# RAILbooster.net
KiCad netlist of a schematic drawn in EAGLE
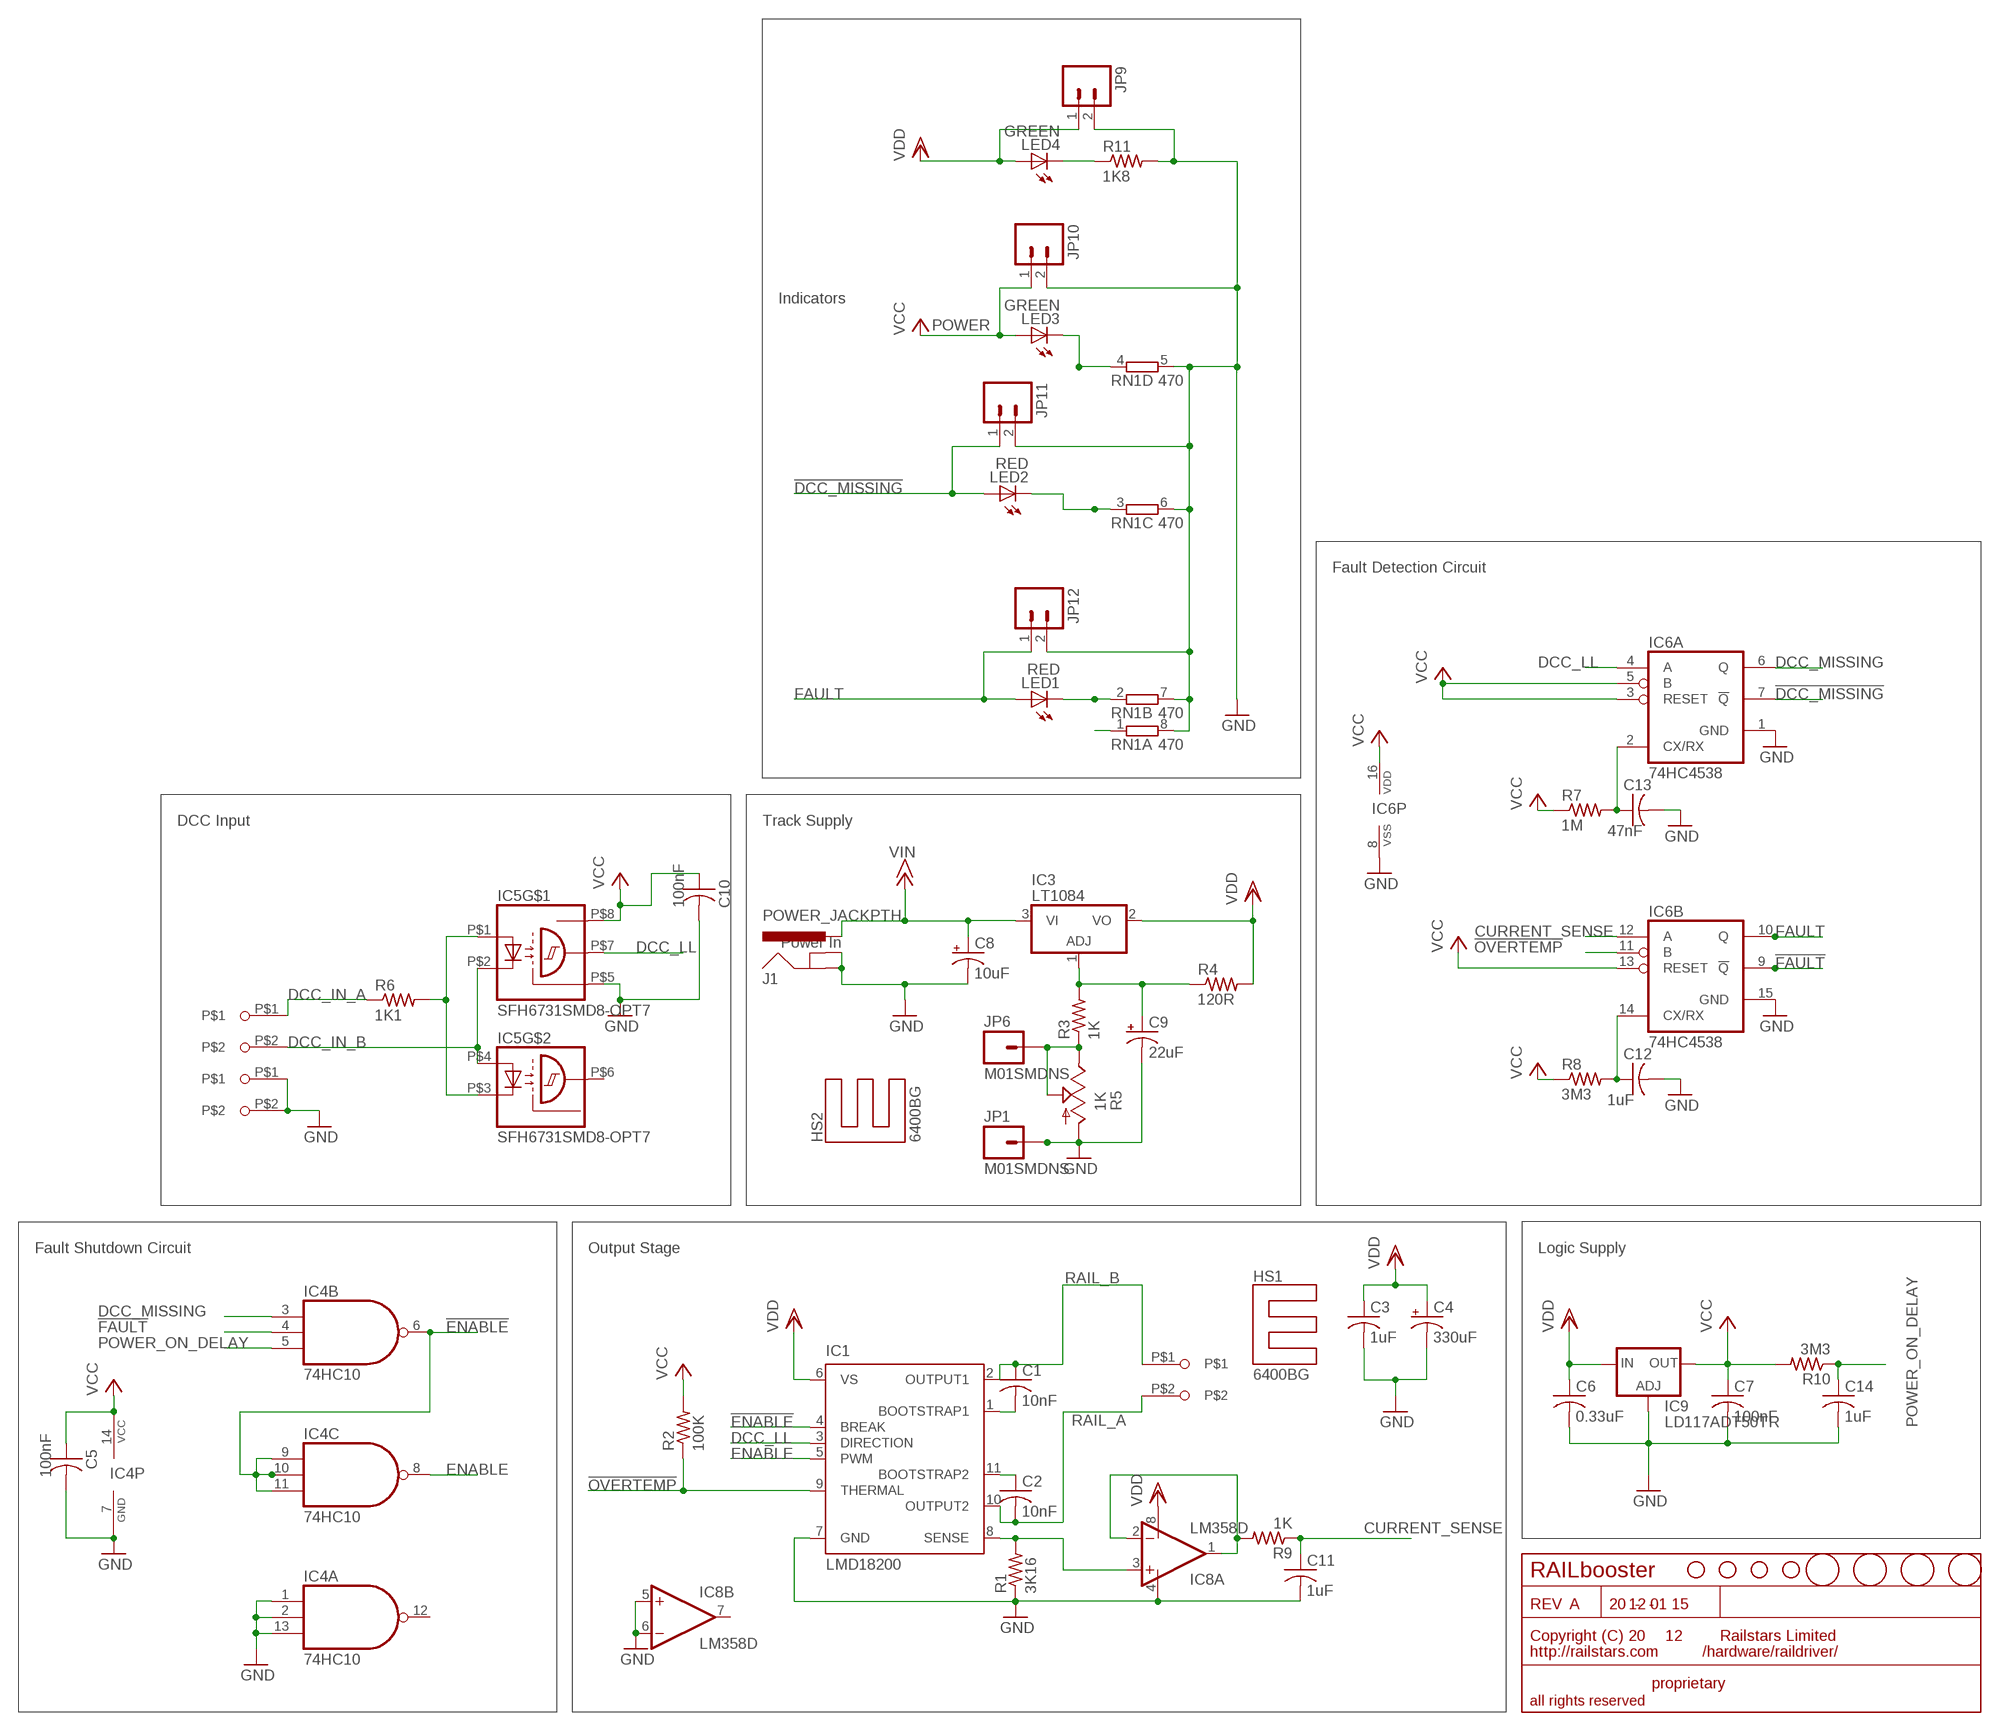
[diagram p0: schematic, sheet 1]

(export (version "E")
  (design (tool "Eeschema 10.0.6"))
  (components
    (comp (ref "C1")
      (value "10nF")
      (footprint "eagle-import:C0603")
      (libsource (lib "eagle-import") (part "C-USC0603"))
    )
    (comp (ref "C2")
      (value "10nF")
      (footprint "eagle-import:C0603")
      (libsource (lib "eagle-import") (part "C-USC0603"))
    )
    (comp (ref "C3")
      (value "1uF")
      (footprint "eagle-import:C0603")
      (libsource (lib "eagle-import") (part "C-USC0603"))
    )
    (comp (ref "C4")
      (value "330uF")
      (footprint "eagle-import:E5-10,5")
      (libsource (lib "eagle-import") (part "CPOL-USE5-10.5"))
    )
    (comp (ref "C5")
      (value "100nF")
      (footprint "eagle-import:C0603")
      (libsource (lib "eagle-import") (part "C-USC0603"))
    )
    (comp (ref "C6")
      (value "0.33uF")
      (footprint "eagle-import:C0603")
      (libsource (lib "eagle-import") (part "C-USC0603"))
    )
    (comp (ref "C7")
      (value "100nF")
      (footprint "eagle-import:C0603")
      (libsource (lib "eagle-import") (part "C-USC0603"))
    )
    (comp (ref "C8")
      (value "10uF")
      (footprint "eagle-import:E2-5")
      (libsource (lib "eagle-import") (part "CPOL-USE2-5"))
    )
    (comp (ref "C9")
      (value "22uF")
      (footprint "eagle-import:E2-5")
      (libsource (lib "eagle-import") (part "CPOL-USE2-5"))
    )
    (comp (ref "C10")
      (value "100nF")
      (footprint "eagle-import:C0603")
      (libsource (lib "eagle-import") (part "C-USC0603"))
    )
    (comp (ref "C11")
      (value "1uF")
      (footprint "eagle-import:C0603")
      (libsource (lib "eagle-import") (part "C-USC0603"))
    )
    (comp (ref "C12")
      (value "1uF")
      (footprint "eagle-import:C0603")
      (libsource (lib "eagle-import") (part "C-USC0603"))
    )
    (comp (ref "C13")
      (value "47nF")
      (footprint "eagle-import:C0603")
      (libsource (lib "eagle-import") (part "C-USC0603"))
    )
    (comp (ref "C14")
      (value "1uF")
      (footprint "eagle-import:C0603")
      (libsource (lib "eagle-import") (part "C-USC0603"))
    )
    (comp (ref "HS1")
      (value "6400BG")
      (footprint "eagle-import:6400BG")
      (libsource (lib "eagle-import") (part "HEATSINK6400BG"))
    )
    (comp (ref "HS2")
      (value "6400BG")
      (footprint "eagle-import:6400BG")
      (libsource (lib "eagle-import") (part "HEATSINK6400BG"))
    )
    (comp (ref "IC1")
      (value "LMD18200")
      (footprint "eagle-import:TO-220-11")
      (libsource (lib "eagle-import") (part "LM18200T"))
    )
    (comp (ref "IC3")
      (value "LT1084")
      (footprint "eagle-import:TO-220")
      (libsource (lib "eagle-import") (part "LT1084CT"))
    )
    (comp (ref "IC4")
      (value "74HC10")
      (footprint "eagle-import:SO14")
      (libsource (lib "eagle-import") (part "7410D"))
    )
    (comp (ref "IC5")
      (value "SFH6731SMD8-OPT7")
      (footprint "eagle-import:SMD8-OPT7")
      (libsource (lib "eagle-import") (part "SFH6731SMD8-OPT7"))
    )
    (comp (ref "IC6")
      (value "74HC4538")
      (footprint "eagle-import:SOIC-16")
      (libsource (lib "eagle-import") (part "74HC4538SOIC"))
    )
    (comp (ref "IC8")
      (value "LM358D")
      (footprint "eagle-import:SO08")
      (libsource (lib "eagle-import") (part "LM358D"))
    )
    (comp (ref "IC9")
      (value "LD117ADT50TR")
      (footprint "eagle-import:DPACK")
      (libsource (lib "eagle-import") (part "LD117A?DT50TR"))
    )
    (comp (ref "J1")
      (value "POWER_JACKPTH")
      (footprint "eagle-import:POWER_JACK_PTH")
      (libsource (lib "eagle-import") (part "POWER_JACKPTH"))
    )
    (comp (ref "JP1")
      (value "M01SMDNS")
      (footprint "eagle-import:1X01NS")
      (libsource (lib "eagle-import") (part "M01SMDNS"))
    )
    (comp (ref "JP2")
      (value "STAND-OFF")
      (footprint "eagle-import:STAND-OFF")
      (libsource (lib "eagle-import") (part "STAND-OFF"))
    )
    (comp (ref "JP3")
      (value "STAND-OFF")
      (footprint "eagle-import:STAND-OFF")
      (libsource (lib "eagle-import") (part "STAND-OFF"))
    )
    (comp (ref "JP4")
      (value "STAND-OFF")
      (footprint "eagle-import:STAND-OFF")
      (libsource (lib "eagle-import") (part "STAND-OFF"))
    )
    (comp (ref "JP5")
      (value "STAND-OFF")
      (footprint "eagle-import:STAND-OFF")
      (libsource (lib "eagle-import") (part "STAND-OFF"))
    )
    (comp (ref "JP6")
      (value "M01SMDNS")
      (footprint "eagle-import:1X01NS")
      (libsource (lib "eagle-import") (part "M01SMDNS"))
    )
    (comp (ref "JP9")
      (value "M02PTH")
      (footprint "eagle-import:1X02")
      (libsource (lib "eagle-import") (part "M02PTH"))
    )
    (comp (ref "JP10")
      (value "M02PTH")
      (footprint "eagle-import:1X02")
      (libsource (lib "eagle-import") (part "M02PTH"))
    )
    (comp (ref "JP11")
      (value "M02PTH")
      (footprint "eagle-import:1X02")
      (libsource (lib "eagle-import") (part "M02PTH"))
    )
    (comp (ref "JP12")
      (value "M02PTH")
      (footprint "eagle-import:1X02")
      (libsource (lib "eagle-import") (part "M02PTH"))
    )
    (comp (ref "LED1")
      (value "RED")
      (footprint "eagle-import:LED-0603")
      (libsource (lib "eagle-import") (part "LED0603"))
    )
    (comp (ref "LED2")
      (value "RED")
      (footprint "eagle-import:LED-0603")
      (libsource (lib "eagle-import") (part "LED0603"))
    )
    (comp (ref "LED3")
      (value "GREEN")
      (footprint "eagle-import:LED-0603")
      (libsource (lib "eagle-import") (part "LED0603"))
    )
    (comp (ref "LED4")
      (value "GREEN")
      (footprint "eagle-import:LED-0603")
      (libsource (lib "eagle-import") (part "LED0603"))
    )
    (comp (ref "R1")
      (value "3K16")
      (footprint "eagle-import:R0603")
      (libsource (lib "eagle-import") (part "R-US_R0603"))
    )
    (comp (ref "R2")
      (value "100K")
      (footprint "eagle-import:R0603")
      (libsource (lib "eagle-import") (part "R-US_R0603"))
    )
    (comp (ref "R3")
      (value "1K")
      (footprint "eagle-import:R1206")
      (libsource (lib "eagle-import") (part "R-US_R1206"))
    )
    (comp (ref "R4")
      (value "120R")
      (footprint "eagle-import:R0603")
      (libsource (lib "eagle-import") (part "R-US_R0603"))
    )
    (comp (ref "R5")
      (value "1K")
      (footprint "eagle-import:S64W")
      (libsource (lib "eagle-import") (part "TRIM_US-S64W"))
    )
    (comp (ref "R6")
      (value "1K1")
      (footprint "eagle-import:R1206")
      (libsource (lib "eagle-import") (part "R-US_R1206"))
    )
    (comp (ref "R7")
      (value "1M")
      (footprint "eagle-import:R0603")
      (libsource (lib "eagle-import") (part "R-US_R0603"))
    )
    (comp (ref "R8")
      (value "3M3")
      (footprint "eagle-import:R0603")
      (libsource (lib "eagle-import") (part "R-US_R0603"))
    )
    (comp (ref "R9")
      (value "1K")
      (footprint "eagle-import:R1206")
      (libsource (lib "eagle-import") (part "R-US_R1206"))
    )
    (comp (ref "R10")
      (value "3M3")
      (footprint "eagle-import:R0603")
      (libsource (lib "eagle-import") (part "R-US_R0603"))
    )
    (comp (ref "R11")
      (value "1K8")
      (footprint "eagle-import:R1206")
      (libsource (lib "eagle-import") (part "R-US_R1206"))
    )
    (comp (ref "RN1")
      (value "470")
      (footprint "eagle-import:EXBS8V")
      (libsource (lib "eagle-import") (part "4R-NEXBS8V"))
    )
    (comp (ref "U$1")
      (value "RAILSTARS_LOGO20MM")
      (footprint "eagle-import:RAILSTARS_1IN")
      (libsource (lib "eagle-import") (part "RAILSTARS_LOGO20MM"))
    )
    (comp (ref "U$5")
      (value "FIDUCIAL")
      (footprint "eagle-import:FIDUCIAL_1MM")
      (libsource (lib "eagle-import") (part "FIDUCIAL"))
    )
    (comp (ref "U$6")
      (value "FIDUCIAL")
      (footprint "eagle-import:FIDUCIAL_1MM")
      (libsource (lib "eagle-import") (part "FIDUCIAL"))
    )
    (comp (ref "U$7")
      (value "FIDUCIAL")
      (footprint "eagle-import:FIDUCIAL_1MM")
      (libsource (lib "eagle-import") (part "FIDUCIAL"))
    )
    (comp (ref "U$8")
      (value "FIDUCIAL")
      (footprint "eagle-import:FIDUCIAL_1MM")
      (libsource (lib "eagle-import") (part "FIDUCIAL"))
    )
    (comp (ref "X1")
      (value "SCREWTERMINAL-5.08-2")
      (footprint "eagle-import:SCREWTERMINAL-5.08-2")
      (libsource (lib "eagle-import") (part "SCREWTERMINAL-5.08-2"))
    )
    (comp (ref "X3")
      (value "SCREWTERMINAL-5.08-2")
      (footprint "eagle-import:SCREWTERMINAL-5.08-2")
      (libsource (lib "eagle-import") (part "SCREWTERMINAL-5.08-2"))
    )
    (comp (ref "X4")
      (value "SCREWTERMINAL-5.08-2")
      (footprint "eagle-import:SCREWTERMINAL-5.08-2")
      (libsource (lib "eagle-import") (part "SCREWTERMINAL-5.08-2"))
    )
  )
  (nets
    (net (code "1") (name "/CURRENT_SENSE") (class "Default")
      (node (ref "C11") (pin "1") (pinfunction "1_1") (pintype "passive"))
      (node (ref "IC6") (pin "12") (pinfunction "A_12") (pintype "input"))
      (node (ref "R9") (pin "1") (pinfunction "1_1") (pintype "passive"))
    )
    (net (code "2") (name "/DCC_IN_A") (class "Default")
      (node (ref "R6") (pin "1") (pinfunction "1_1") (pintype "passive"))
      (node (ref "X1") (pin "P$1") (pinfunction "P$1_P$1") (pintype "bidirectional"))
    )
    (net (code "3") (name "/DCC_IN_B") (class "Default")
      (node (ref "IC5") (pin "P$2") (pinfunction "C_P$2") (pintype "passive"))
      (node (ref "IC5") (pin "P$4") (pinfunction "A_P$4") (pintype "passive"))
      (node (ref "X1") (pin "P$2") (pinfunction "P$2_P$2") (pintype "bidirectional"))
    )
    (net (code "4") (name "/DCC_LL") (class "Default")
      (node (ref "IC1") (pin "3") (pinfunction "DIRECTION_3") (pintype "input"))
      (node (ref "IC5") (pin "P$7") (pinfunction "OUT_P$7") (pintype "passive"))
      (node (ref "IC6") (pin "4") (pinfunction "A_4") (pintype "input"))
    )
    (net (code "5") (name "/DCC_MISSING") (class "Default")
      (node (ref "IC4") (pin "3") (pinfunction "I0_3") (pintype "input"))
      (node (ref "IC6") (pin "6") (pinfunction "Q_6") (pintype "output"))
    )
    (net (code "6") (name "/ENABLE") (class "Default")
      (node (ref "IC1") (pin "5") (pinfunction "PWM_5") (pintype "input"))
      (node (ref "IC4") (pin "8") (pinfunction "O_8") (pintype "output"))
    )
    (net (code "7") (name "/FAULT") (class "Default")
      (node (ref "IC6") (pin "10") (pinfunction "Q_10") (pintype "output"))
      (node (ref "JP12") (pin "1") (pinfunction "1_1") (pintype "passive"))
      (node (ref "LED1") (pin "A") (pinfunction "A_A") (pintype "passive"))
    )
    (net (code "8") (name "/POWER_ON_DELAY") (class "Default")
      (node (ref "C14") (pin "1") (pinfunction "1_1") (pintype "passive"))
      (node (ref "IC4") (pin "5") (pinfunction "I2_5") (pintype "input"))
      (node (ref "R10") (pin "1") (pinfunction "1_1") (pintype "passive"))
    )
    (net (code "9") (name "/RAIL_A") (class "Default")
      (node (ref "C2") (pin "2") (pinfunction "2_2") (pintype "passive"))
      (node (ref "IC1") (pin "10") (pinfunction "OUTPUT2_10") (pintype "output"))
      (node (ref "X4") (pin "P$2") (pinfunction "P$2_P$2") (pintype "bidirectional"))
    )
    (net (code "10") (name "/RAIL_B") (class "Default")
      (node (ref "C1") (pin "1") (pinfunction "1_1") (pintype "passive"))
      (node (ref "IC1") (pin "2") (pinfunction "OUTPUT1_2") (pintype "output"))
      (node (ref "X4") (pin "P$1") (pinfunction "P$1_P$1") (pintype "bidirectional"))
    )
    (net (code "11") (name "/~{DCC_MISSING}") (class "Default")
      (node (ref "IC6") (pin "7") (pinfunction "~{Q}_7") (pintype "output"))
      (node (ref "JP11") (pin "1") (pinfunction "1_1") (pintype "passive"))
      (node (ref "LED2") (pin "A") (pinfunction "A_A") (pintype "passive"))
    )
    (net (code "12") (name "/~{ENABLE}") (class "Default")
      (node (ref "IC1") (pin "4") (pinfunction "BREAK_4") (pintype "input"))
      (node (ref "IC4") (pin "10") (pinfunction "I1_10") (pintype "input"))
      (node (ref "IC4") (pin "11") (pinfunction "I2_11") (pintype "input"))
      (node (ref "IC4") (pin "6") (pinfunction "O_6") (pintype "output"))
      (node (ref "IC4") (pin "9") (pinfunction "I0_9") (pintype "input"))
    )
    (net (code "13") (name "/~{FAULT}") (class "Default")
      (node (ref "IC4") (pin "4") (pinfunction "I1_4") (pintype "input"))
      (node (ref "IC6") (pin "9") (pinfunction "~{Q}_9") (pintype "output"))
    )
    (net (code "14") (name "/~{OVERTEMP}") (class "Default")
      (node (ref "IC1") (pin "9") (pinfunction "THERMAL_9") (pintype "output"))
      (node (ref "IC6") (pin "11") (pinfunction "B_11") (pintype "input"))
      (node (ref "R2") (pin "1") (pinfunction "1_1") (pintype "passive"))
    )
    (net (code "15") (name "GND") (class "Default")
      (node (ref "C10") (pin "2") (pinfunction "2_2") (pintype "passive"))
      (node (ref "C11") (pin "2") (pinfunction "2_2") (pintype "passive"))
      (node (ref "C12") (pin "2") (pinfunction "2_2") (pintype "passive"))
      (node (ref "C13") (pin "2") (pinfunction "2_2") (pintype "passive"))
      (node (ref "C14") (pin "2") (pinfunction "2_2") (pintype "passive"))
      (node (ref "C3") (pin "2") (pinfunction "2_2") (pintype "passive"))
      (node (ref "C4") (pin "-") (pinfunction "-_-") (pintype "passive"))
      (node (ref "C5") (pin "2") (pinfunction "2_2") (pintype "passive"))
      (node (ref "C6") (pin "2") (pinfunction "2_2") (pintype "passive"))
      (node (ref "C7") (pin "2") (pinfunction "2_2") (pintype "passive"))
      (node (ref "C8") (pin "-") (pinfunction "-_-") (pintype "passive"))
      (node (ref "C9") (pin "-") (pinfunction "-_-") (pintype "passive"))
      (node (ref "IC1") (pin "7") (pinfunction "GND_7") (pintype "power_in"))
      (node (ref "IC4") (pin "1") (pinfunction "I0_1") (pintype "input"))
      (node (ref "IC4") (pin "13") (pinfunction "I2_13") (pintype "input"))
      (node (ref "IC4") (pin "2") (pinfunction "I1_2") (pintype "input"))
      (node (ref "IC4") (pin "7") (pinfunction "GND_7") (pintype "power_in"))
      (node (ref "IC5") (pin "P$5") (pinfunction "GND_P$5") (pintype "passive"))
      (node (ref "IC6") (pin "1") (pinfunction "GND_1") (pintype "input"))
      (node (ref "IC6") (pin "15") (pinfunction "GND_15") (pintype "input"))
      (node (ref "IC6") (pin "8") (pinfunction "VSS_8") (pintype "power_in"))
      (node (ref "IC8") (pin "4") (pinfunction "V-_4") (pintype "power_in"))
      (node (ref "IC8") (pin "5") (pinfunction "+IN_5") (pintype "input"))
      (node (ref "IC8") (pin "6") (pinfunction "-IN_6") (pintype "input"))
      (node (ref "IC9") (pin "1") (pinfunction "ADJ_1") (pintype "input"))
      (node (ref "J1") (pin "GND") (pinfunction "GND_GND") (pintype "bidirectional"))
      (node (ref "J1") (pin "GNDBREAK") (pinfunction "GNDBREAK_GNDBREAK") (pintype "bidirectional"))
      (node (ref "JP1") (pin "1") (pinfunction "1_1") (pintype "passive"))
      (node (ref "JP10") (pin "2") (pinfunction "2_2") (pintype "passive"))
      (node (ref "JP11") (pin "2") (pinfunction "2_2") (pintype "passive"))
      (node (ref "JP12") (pin "2") (pinfunction "2_2") (pintype "passive"))
      (node (ref "JP9") (pin "2") (pinfunction "2_2") (pintype "passive"))
      (node (ref "R1") (pin "1") (pinfunction "1_1") (pintype "passive"))
      (node (ref "R11") (pin "2") (pinfunction "2_2") (pintype "passive"))
      (node (ref "R5") (pin "A") (pinfunction "A_A") (pintype "passive"))
      (node (ref "RN1") (pin "5") (pinfunction "2_5") (pintype "passive"))
      (node (ref "RN1") (pin "6") (pinfunction "2_6") (pintype "passive"))
      (node (ref "RN1") (pin "7") (pinfunction "2_7") (pintype "passive"))
      (node (ref "RN1") (pin "8") (pinfunction "2_8") (pintype "passive"))
      (node (ref "X3") (pin "P$1") (pinfunction "P$1_P$1") (pintype "bidirectional"))
      (node (ref "X3") (pin "P$2") (pinfunction "P$2_P$2") (pintype "bidirectional"))
    )
    (net (code "16") (name "Net-(IC1-BOOTSTRAP1)") (class "Default")
      (node (ref "C1") (pin "2") (pinfunction "2_2") (pintype "passive"))
      (node (ref "IC1") (pin "1") (pinfunction "BOOTSTRAP1_1") (pintype "input"))
    )
    (net (code "17") (name "Net-(IC1-BOOTSTRAP2)") (class "Default")
      (node (ref "C2") (pin "1") (pinfunction "1_1") (pintype "passive"))
      (node (ref "IC1") (pin "11") (pinfunction "BOOTSTRAP2_11") (pintype "input"))
    )
    (net (code "18") (name "Net-(IC1-SENSE)") (class "Default")
      (node (ref "IC1") (pin "8") (pinfunction "SENSE_8") (pintype "output"))
      (node (ref "IC8") (pin "3") (pinfunction "+IN_3") (pintype "input"))
      (node (ref "R1") (pin "2") (pinfunction "2_2") (pintype "passive"))
    )
    (net (code "19") (name "Net-(IC3-ADJ)") (class "Default")
      (node (ref "C9") (pin "+") (pinfunction "+_+") (pintype "passive"))
      (node (ref "IC3") (pin "1") (pinfunction "ADJ_1") (pintype "input"))
      (node (ref "R3") (pin "2") (pinfunction "2_2") (pintype "passive"))
      (node (ref "R4") (pin "1") (pinfunction "1_1") (pintype "passive"))
    )
    (net (code "20") (name "Net-(IC5A-A)") (class "Default")
      (node (ref "IC5") (pin "P$1") (pinfunction "A_P$1") (pintype "passive"))
      (node (ref "IC5") (pin "P$3") (pinfunction "C_P$3") (pintype "passive"))
      (node (ref "R6") (pin "2") (pinfunction "2_2") (pintype "passive"))
    )
    (net (code "21") (name "Net-(IC6A-CX{slash}RX)") (class "Default")
      (node (ref "C13") (pin "1") (pinfunction "1_1") (pintype "passive"))
      (node (ref "IC6") (pin "2") (pinfunction "CX/RX_2") (pintype "input"))
      (node (ref "R7") (pin "2") (pinfunction "2_2") (pintype "passive"))
    )
    (net (code "22") (name "Net-(IC6B-CX{slash}RX)") (class "Default")
      (node (ref "C12") (pin "1") (pinfunction "1_1") (pintype "passive"))
      (node (ref "IC6") (pin "14") (pinfunction "CX/RX_14") (pintype "input"))
      (node (ref "R8") (pin "2") (pinfunction "2_2") (pintype "passive"))
    )
    (net (code "23") (name "Net-(IC8A--IN)") (class "Default")
      (node (ref "IC8") (pin "1") (pinfunction "OUT_1") (pintype "output"))
      (node (ref "IC8") (pin "2") (pinfunction "-IN_2") (pintype "input"))
      (node (ref "R9") (pin "2") (pinfunction "2_2") (pintype "passive"))
    )
    (net (code "24") (name "Net-(JP6-Pad1)") (class "Default")
      (node (ref "JP6") (pin "1") (pinfunction "1_1") (pintype "passive"))
      (node (ref "R3") (pin "1") (pinfunction "1_1") (pintype "passive"))
      (node (ref "R5") (pin "E") (pinfunction "E_E") (pintype "passive"))
      (node (ref "R5") (pin "S") (pinfunction "S_S") (pintype "passive"))
    )
    (net (code "25") (name "Net-(LED4-PadC)") (class "Default")
      (node (ref "LED4") (pin "C") (pinfunction "C_C") (pintype "passive"))
      (node (ref "R11") (pin "1") (pinfunction "1_1") (pintype "passive"))
    )
    (net (code "26") (name "Net-(RN1B-1)") (class "Default")
      (node (ref "LED1") (pin "C") (pinfunction "C_C") (pintype "passive"))
      (node (ref "RN1") (pin "2") (pinfunction "1_2") (pintype "passive"))
    )
    (net (code "27") (name "Net-(RN1C-1)") (class "Default")
      (node (ref "LED2") (pin "C") (pinfunction "C_C") (pintype "passive"))
      (node (ref "RN1") (pin "3") (pinfunction "1_3") (pintype "passive"))
    )
    (net (code "28") (name "Net-(RN1D-1)") (class "Default")
      (node (ref "LED3") (pin "C") (pinfunction "C_C") (pintype "passive"))
      (node (ref "RN1") (pin "4") (pinfunction "1_4") (pintype "passive"))
    )
    (net (code "29") (name "VCC") (class "Default")
      (node (ref "C10") (pin "1") (pinfunction "1_1") (pintype "passive"))
      (node (ref "C5") (pin "1") (pinfunction "1_1") (pintype "passive"))
      (node (ref "C7") (pin "1") (pinfunction "1_1") (pintype "passive"))
      (node (ref "IC4") (pin "14") (pinfunction "VCC_14") (pintype "power_in"))
      (node (ref "IC5") (pin "P$8") (pinfunction "VCC_P$8") (pintype "passive"))
      (node (ref "IC6") (pin "13") (pinfunction "RESET_13") (pintype "input"))
      (node (ref "IC6") (pin "16") (pinfunction "VDD_16") (pintype "power_in"))
      (node (ref "IC6") (pin "3") (pinfunction "RESET_3") (pintype "input"))
      (node (ref "IC6") (pin "5") (pinfunction "B_5") (pintype "input"))
      (node (ref "IC9") (pin "4") (pinfunction "OUT_4") (pintype "passive"))
      (node (ref "JP10") (pin "1") (pinfunction "1_1") (pintype "passive"))
      (node (ref "LED3") (pin "A") (pinfunction "A_A") (pintype "passive"))
      (node (ref "R10") (pin "2") (pinfunction "2_2") (pintype "passive"))
      (node (ref "R2") (pin "2") (pinfunction "2_2") (pintype "passive"))
      (node (ref "R7") (pin "1") (pinfunction "1_1") (pintype "passive"))
      (node (ref "R8") (pin "1") (pinfunction "1_1") (pintype "passive"))
    )
    (net (code "30") (name "VDD") (class "Default")
      (node (ref "C3") (pin "1") (pinfunction "1_1") (pintype "passive"))
      (node (ref "C4") (pin "+") (pinfunction "+_+") (pintype "passive"))
      (node (ref "C6") (pin "1") (pinfunction "1_1") (pintype "passive"))
      (node (ref "IC1") (pin "6") (pinfunction "VS_6") (pintype "power_in"))
      (node (ref "IC3") (pin "2") (pinfunction "VO_2") (pintype "passive"))
      (node (ref "IC8") (pin "8") (pinfunction "V+_8") (pintype "power_in"))
      (node (ref "IC9") (pin "3") (pinfunction "IN_3") (pintype "input"))
      (node (ref "JP9") (pin "1") (pinfunction "1_1") (pintype "passive"))
      (node (ref "LED4") (pin "A") (pinfunction "A_A") (pintype "passive"))
      (node (ref "R4") (pin "2") (pinfunction "2_2") (pintype "passive"))
    )
    (net (code "31") (name "VIN") (class "Default")
      (node (ref "C8") (pin "+") (pinfunction "+_+") (pintype "passive"))
      (node (ref "IC3") (pin "3") (pinfunction "VI_3") (pintype "input"))
      (node (ref "J1") (pin "PWR") (pinfunction "PWR_PWR") (pintype "bidirectional"))
    )
    (net (code "32") (name "unconnected-(IC4A-O-Pad12)") (class "Default")
      (node (ref "IC4") (pin "12") (pinfunction "O_12") (pintype "output"))
    )
    (net (code "33") (name "unconnected-(IC5B-OUT-PadP$6)") (class "Default")
      (node (ref "IC5") (pin "P$6") (pinfunction "OUT_P$6") (pintype "passive"))
    )
    (net (code "34") (name "unconnected-(IC8B-OUT-Pad7)") (class "Default")
      (node (ref "IC8") (pin "7") (pinfunction "OUT_7") (pintype "output"))
    )
    (net (code "35") (name "unconnected-(RN1-Pad1)") (class "Default")
      (node (ref "RN1") (pin "1") (pinfunction "1_1") (pintype "passive"))
    )
  )
)
